# transistor_op-amp_v2.net
KiCad netlist of a schematic drawn in EAGLE
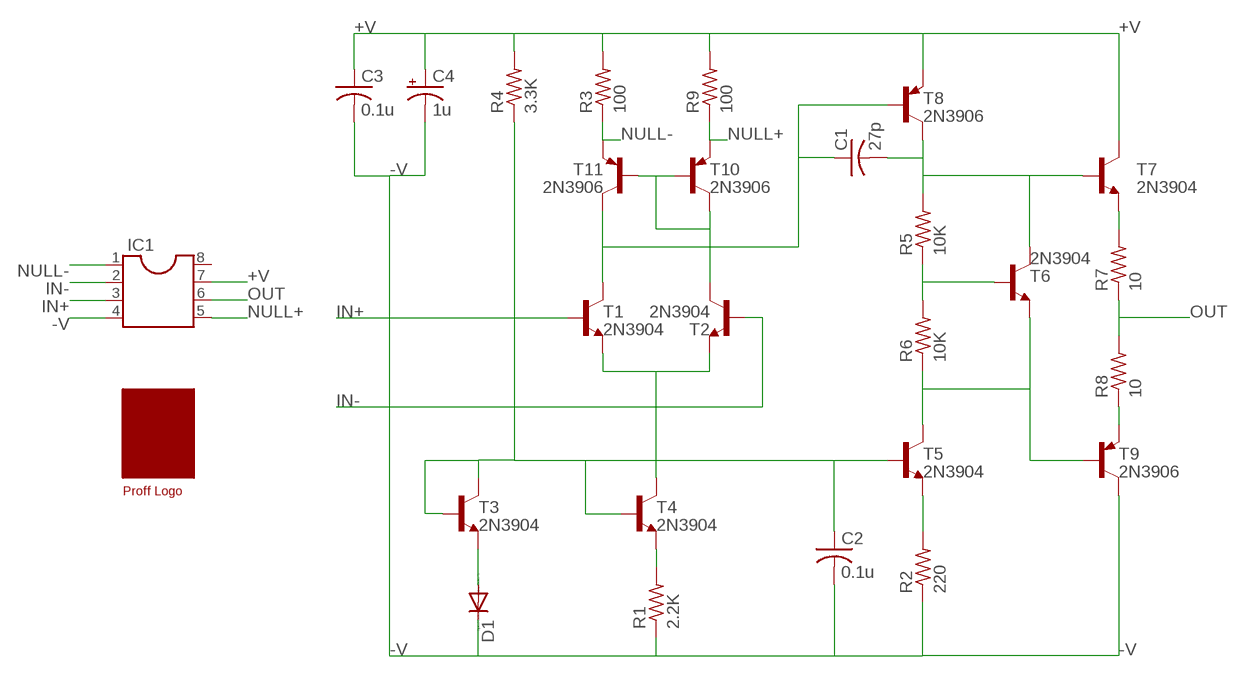
[diagram p0: schematic, sheet 1]

(export (version "E")
  (design (tool "Eeschema 10.0.6"))
  (components
    (comp (ref "C1")
      (value "27p")
      (footprint "eagle-import:C050-024X044")
      (libsource (lib "eagle-import") (part "C-US050-024X044"))
    )
    (comp (ref "C2")
      (value "0.1u")
      (footprint "eagle-import:C050-024X044")
      (libsource (lib "eagle-import") (part "C-US050-024X044"))
    )
    (comp (ref "C3")
      (value "0.1u")
      (footprint "eagle-import:C050-024X044")
      (libsource (lib "eagle-import") (part "C-US050-024X044"))
    )
    (comp (ref "C4")
      (value "1u")
      (footprint "eagle-import:E2,5-5")
      (libsource (lib "eagle-import") (part "CPOL-USE2.5-5"))
    )
    (comp (ref "D1")
      (value "DIODE-D-7.5")
      (footprint "eagle-import:D-7.5")
      (libsource (lib "eagle-import") (part "DIODE-D-7.5"))
    )
    (comp (ref "IC1")
      (value "DIL8S")
      (footprint "eagle-import:SOCKET-08")
      (libsource (lib "eagle-import") (part "DIL8S"))
    )
    (comp (ref "R1")
      (value "2.2K")
      (footprint "eagle-import:0207_7")
      (libsource (lib "eagle-import") (part "R-US_0207/7"))
    )
    (comp (ref "R2")
      (value "220")
      (footprint "eagle-import:0207_7")
      (libsource (lib "eagle-import") (part "R-US_0207/7"))
    )
    (comp (ref "R3")
      (value "100")
      (footprint "eagle-import:0207_7")
      (libsource (lib "eagle-import") (part "R-US_0207/7"))
    )
    (comp (ref "R4")
      (value "3.3K")
      (footprint "eagle-import:0207_7")
      (libsource (lib "eagle-import") (part "R-US_0207/7"))
    )
    (comp (ref "R5")
      (value "10K")
      (footprint "eagle-import:0207_7")
      (libsource (lib "eagle-import") (part "R-US_0207/7"))
    )
    (comp (ref "R6")
      (value "10K")
      (footprint "eagle-import:0207_7")
      (libsource (lib "eagle-import") (part "R-US_0207/7"))
    )
    (comp (ref "R7")
      (value "10")
      (footprint "eagle-import:0207_7")
      (libsource (lib "eagle-import") (part "R-US_0207/7"))
    )
    (comp (ref "R8")
      (value "10")
      (footprint "eagle-import:0207_7")
      (libsource (lib "eagle-import") (part "R-US_0207/7"))
    )
    (comp (ref "R9")
      (value "100")
      (footprint "eagle-import:0207_7")
      (libsource (lib "eagle-import") (part "R-US_0207/7"))
    )
    (comp (ref "T1")
      (value "2N3904")
      (footprint "eagle-import:TO92")
      (libsource (lib "eagle-import") (part "2N3904"))
    )
    (comp (ref "T2")
      (value "2N3904")
      (footprint "eagle-import:TO92")
      (libsource (lib "eagle-import") (part "2N3904"))
    )
    (comp (ref "T3")
      (value "2N3904")
      (footprint "eagle-import:TO92")
      (libsource (lib "eagle-import") (part "2N3904"))
    )
    (comp (ref "T4")
      (value "2N3904")
      (footprint "eagle-import:TO92")
      (libsource (lib "eagle-import") (part "2N3904"))
    )
    (comp (ref "T5")
      (value "2N3904")
      (footprint "eagle-import:TO92")
      (libsource (lib "eagle-import") (part "2N3904"))
    )
    (comp (ref "T6")
      (value "2N3904")
      (footprint "eagle-import:TO92")
      (libsource (lib "eagle-import") (part "2N3904"))
    )
    (comp (ref "T7")
      (value "2N3904")
      (footprint "eagle-import:TO92")
      (libsource (lib "eagle-import") (part "transistor-npn_2N3904"))
    )
    (comp (ref "T8")
      (value "2N3906")
      (footprint "eagle-import:TO92")
      (libsource (lib "eagle-import") (part "2N3906"))
    )
    (comp (ref "T9")
      (value "2N3906")
      (footprint "eagle-import:TO92")
      (libsource (lib "eagle-import") (part "2N3906"))
    )
    (comp (ref "T10")
      (value "2N3906")
      (footprint "eagle-import:TO92")
      (libsource (lib "eagle-import") (part "2N3906"))
    )
    (comp (ref "T11")
      (value "2N3906")
      (footprint "eagle-import:TO92")
      (libsource (lib "eagle-import") (part "2N3906"))
    )
    (comp (ref "U$1")
      (value "PROFF")
      (footprint "eagle-import:PROFF")
      (libsource (lib "eagle-import") (part "PROFF"))
    )
  )
  (nets
    (net (code "1") (name "/+V") (class "Default")
      (node (ref "C3") (pin "1") (pinfunction "1_1") (pintype "passive"))
      (node (ref "C4") (pin "+") (pinfunction "+_+") (pintype "passive"))
      (node (ref "IC1") (pin "7") (pinfunction "7_7") (pintype "passive"))
      (node (ref "R3") (pin "2") (pinfunction "2_2") (pintype "passive"))
      (node (ref "R4") (pin "2") (pinfunction "2_2") (pintype "passive"))
      (node (ref "R9") (pin "2") (pinfunction "2_2") (pintype "passive"))
      (node (ref "T7") (pin "1") (pinfunction "C_1") (pintype "passive"))
      (node (ref "T8") (pin "3") (pinfunction "E_3") (pintype "passive"))
    )
    (net (code "2") (name "/-V") (class "Default")
      (node (ref "C2") (pin "2") (pinfunction "2_2") (pintype "passive"))
      (node (ref "C3") (pin "2") (pinfunction "2_2") (pintype "passive"))
      (node (ref "C4") (pin "-") (pinfunction "-_-") (pintype "passive"))
      (node (ref "D1") (pin "C") (pinfunction "C_C") (pintype "passive"))
      (node (ref "IC1") (pin "4") (pinfunction "4_4") (pintype "passive"))
      (node (ref "R1") (pin "1") (pinfunction "1_1") (pintype "passive"))
      (node (ref "R2") (pin "1") (pinfunction "1_1") (pintype "passive"))
      (node (ref "T9") (pin "1") (pinfunction "C_1") (pintype "passive"))
    )
    (net (code "3") (name "/IN+") (class "Default")
      (node (ref "IC1") (pin "3") (pinfunction "3_3") (pintype "passive"))
      (node (ref "T1") (pin "2") (pinfunction "B_2") (pintype "passive"))
    )
    (net (code "4") (name "/IN-") (class "Default")
      (node (ref "IC1") (pin "2") (pinfunction "2_2") (pintype "passive"))
      (node (ref "T2") (pin "2") (pinfunction "B_2") (pintype "passive"))
    )
    (net (code "5") (name "/NULL+") (class "Default")
      (node (ref "IC1") (pin "5") (pinfunction "5_5") (pintype "passive"))
      (node (ref "R9") (pin "1") (pinfunction "1_1") (pintype "passive"))
      (node (ref "T10") (pin "3") (pinfunction "E_3") (pintype "passive"))
    )
    (net (code "6") (name "/NULL-") (class "Default")
      (node (ref "IC1") (pin "1") (pinfunction "1_1") (pintype "passive"))
      (node (ref "R3") (pin "1") (pinfunction "1_1") (pintype "passive"))
      (node (ref "T11") (pin "3") (pinfunction "E_3") (pintype "passive"))
    )
    (net (code "7") (name "/OUT") (class "Default")
      (node (ref "IC1") (pin "6") (pinfunction "6_6") (pintype "passive"))
      (node (ref "R7") (pin "1") (pinfunction "1_1") (pintype "passive"))
      (node (ref "R8") (pin "2") (pinfunction "2_2") (pintype "passive"))
    )
    (net (code "8") (name "Net-(T1-C)") (class "Default")
      (node (ref "C1") (pin "1") (pinfunction "1_1") (pintype "passive"))
      (node (ref "T1") (pin "1") (pinfunction "C_1") (pintype "passive"))
      (node (ref "T11") (pin "1") (pinfunction "C_1") (pintype "passive"))
      (node (ref "T8") (pin "2") (pinfunction "B_2") (pintype "passive"))
    )
    (net (code "9") (name "Net-(T1-E)") (class "Default")
      (node (ref "T1") (pin "3") (pinfunction "E_3") (pintype "passive"))
      (node (ref "T2") (pin "3") (pinfunction "E_3") (pintype "passive"))
      (node (ref "T4") (pin "1") (pinfunction "C_1") (pintype "passive"))
    )
    (net (code "10") (name "Net-(T3-B)") (class "Default")
      (node (ref "C2") (pin "1") (pinfunction "1_1") (pintype "passive"))
      (node (ref "R4") (pin "1") (pinfunction "1_1") (pintype "passive"))
      (node (ref "T3") (pin "1") (pinfunction "C_1") (pintype "passive"))
      (node (ref "T3") (pin "2") (pinfunction "B_2") (pintype "passive"))
      (node (ref "T4") (pin "2") (pinfunction "B_2") (pintype "passive"))
      (node (ref "T5") (pin "2") (pinfunction "B_2") (pintype "passive"))
    )
    (net (code "11") (name "Net-(T3-E)") (class "Default")
      (node (ref "D1") (pin "A") (pinfunction "A_A") (pintype "passive"))
      (node (ref "T3") (pin "3") (pinfunction "E_3") (pintype "passive"))
    )
    (net (code "12") (name "Net-(T4-E)") (class "Default")
      (node (ref "R1") (pin "2") (pinfunction "2_2") (pintype "passive"))
      (node (ref "T4") (pin "3") (pinfunction "E_3") (pintype "passive"))
    )
    (net (code "13") (name "Net-(T5-C)") (class "Default")
      (node (ref "R6") (pin "1") (pinfunction "1_1") (pintype "passive"))
      (node (ref "T5") (pin "1") (pinfunction "C_1") (pintype "passive"))
      (node (ref "T6") (pin "3") (pinfunction "E_3") (pintype "passive"))
      (node (ref "T9") (pin "2") (pinfunction "B_2") (pintype "passive"))
    )
    (net (code "14") (name "Net-(T5-E)") (class "Default")
      (node (ref "R2") (pin "2") (pinfunction "2_2") (pintype "passive"))
      (node (ref "T5") (pin "3") (pinfunction "E_3") (pintype "passive"))
    )
    (net (code "15") (name "Net-(T6-B)") (class "Default")
      (node (ref "R5") (pin "1") (pinfunction "1_1") (pintype "passive"))
      (node (ref "R6") (pin "2") (pinfunction "2_2") (pintype "passive"))
      (node (ref "T6") (pin "2") (pinfunction "B_2") (pintype "passive"))
    )
    (net (code "16") (name "Net-(T6-C)") (class "Default")
      (node (ref "C1") (pin "2") (pinfunction "2_2") (pintype "passive"))
      (node (ref "R5") (pin "2") (pinfunction "2_2") (pintype "passive"))
      (node (ref "T6") (pin "1") (pinfunction "C_1") (pintype "passive"))
      (node (ref "T7") (pin "2") (pinfunction "B_2") (pintype "passive"))
      (node (ref "T8") (pin "1") (pinfunction "C_1") (pintype "passive"))
    )
    (net (code "17") (name "Net-(T7-E)") (class "Default")
      (node (ref "R7") (pin "2") (pinfunction "2_2") (pintype "passive"))
      (node (ref "T7") (pin "3") (pinfunction "E_3") (pintype "passive"))
    )
    (net (code "18") (name "Net-(T9-E)") (class "Default")
      (node (ref "R8") (pin "1") (pinfunction "1_1") (pintype "passive"))
      (node (ref "T9") (pin "3") (pinfunction "E_3") (pintype "passive"))
    )
    (net (code "19") (name "Net-(T10-B)") (class "Default")
      (node (ref "T10") (pin "1") (pinfunction "C_1") (pintype "passive"))
      (node (ref "T10") (pin "2") (pinfunction "B_2") (pintype "passive"))
      (node (ref "T11") (pin "2") (pinfunction "B_2") (pintype "passive"))
      (node (ref "T2") (pin "1") (pinfunction "C_1") (pintype "passive"))
    )
    (net (code "20") (name "unconnected-(IC1-Pad8)") (class "Default")
      (node (ref "IC1") (pin "8") (pinfunction "8_8") (pintype "passive"))
    )
  )
)
